# microbit-motion-tracking.net
KiCad netlist of a schematic drawn in Altium Designer
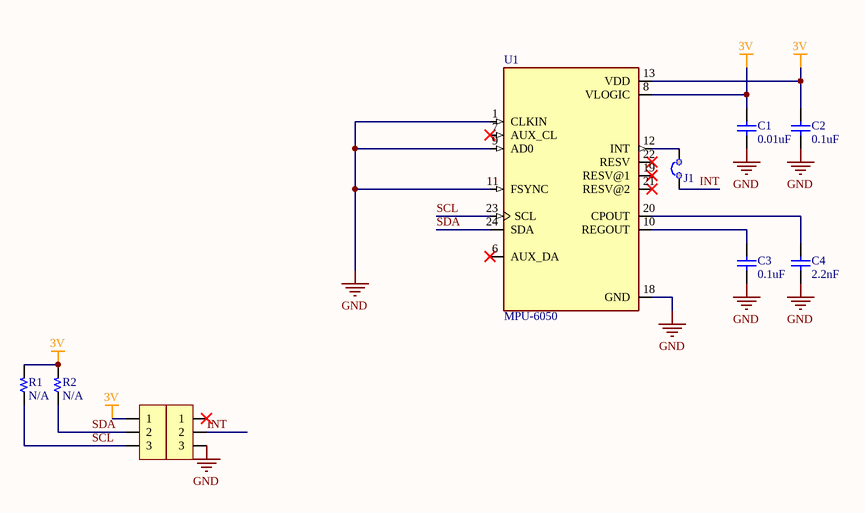
[diagram p0: microbit-motion-tracking.SchDoc]

(export (version "E")
  (design (tool "Eeschema 10.0.6"))
  (components
    (comp (ref "C1")
      (value "0.01uF")
      (footprint "C 0603")
      (description "Capacitor non-pol")
      (libsource (lib "common_altium_libs") (part "Capacitor NP"))
    )
    (comp (ref "C2")
      (value "0.1uF")
      (footprint "C 0603")
      (description "Capacitor non-pol")
      (libsource (lib "common_altium_libs") (part "Capacitor NP"))
    )
    (comp (ref "C3")
      (value "0.1uF")
      (footprint "C 0603")
      (description "Capacitor non-pol")
      (libsource (lib "common_altium_libs") (part "Capacitor NP"))
    )
    (comp (ref "C4")
      (value "2.2nF")
      (footprint "C 0603")
      (description "Capacitor non-pol")
      (libsource (lib "common_altium_libs") (part "Capacitor NP"))
    )
    (comp (ref "J1")
      (value "JUMP 2")
      (footprint "JUMP/2/SMD/D")
      (libsource (lib "common_altium_libs") (part "JUMP 2"))
    )
    (comp (ref "P1")
      (value "Header 3")
      (footprint "HDR/Header/3/c1")
      (description "Header, 3-Pin")
      (libsource (lib "common_altium_libs") (part "Header 3"))
    )
    (comp (ref "P2")
      (value "Header 3")
      (footprint "HDR/Header/3/c1")
      (description "Header, 3-Pin")
      (libsource (lib "") (part "Header 3_1"))
    )
    (comp (ref "R1")
      (value "N/A")
      (footprint "R 0603")
      (description "Resistor")
      (libsource (lib "common_altium_libs") (part "Resistor"))
    )
    (comp (ref "R2")
      (value "N/A")
      (footprint "R 0603")
      (description "Resistor")
      (libsource (lib "common_altium_libs") (part "Resistor"))
    )
    (comp (ref "U1")
      (value "MPU-6050")
      (footprint "QFN 50P 24 400X400X95")
      (description "Accelerometer, Gyroscope, 6 Axis Sensor IÂ²C Output")
      (fields (field (name "MF") "TDK InvenSense"))
      (libsource (lib "common_altium_libs") (part "MPU-6050"))
    )
  )
  (nets
    (net (code "1") (name "/INT") (class "Default")
      (node (ref "J1") (pin "1") (pinfunction "1_1") (pintype "passive"))
      (node (ref "P2") (pin "2") (pinfunction "2_2") (pintype "passive"))
    )
    (net (code "2") (name "/SCL") (class "Default")
      (node (ref "P1") (pin "3") (pinfunction "3_3") (pintype "passive"))
      (node (ref "R1") (pin "1") (pinfunction "1_1") (pintype "passive"))
      (node (ref "U1") (pin "23") (pinfunction "SCL_23") (pintype "input"))
    )
    (net (code "3") (name "/SDA") (class "Default")
      (node (ref "P1") (pin "2") (pinfunction "2_2") (pintype "passive"))
      (node (ref "R2") (pin "1") (pinfunction "1_1") (pintype "passive"))
      (node (ref "U1") (pin "24") (pinfunction "SDA_24") (pintype "bidirectional"))
    )
    (net (code "4") (name "3V") (class "Default")
      (node (ref "C1") (pin "1") (pinfunction "1_1") (pintype "passive"))
      (node (ref "C2") (pin "1") (pinfunction "1_1") (pintype "passive"))
      (node (ref "P1") (pin "1") (pinfunction "1_1") (pintype "passive"))
      (node (ref "R1") (pin "2") (pinfunction "2_2") (pintype "passive"))
      (node (ref "R2") (pin "2") (pinfunction "2_2") (pintype "passive"))
      (node (ref "U1") (pin "13") (pinfunction "VDD_13") (pintype "power_in"))
      (node (ref "U1") (pin "8") (pinfunction "VLOGIC_8") (pintype "power_in"))
    )
    (net (code "5") (name "GND") (class "Default")
      (node (ref "C1") (pin "2") (pinfunction "2_2") (pintype "passive"))
      (node (ref "C2") (pin "2") (pinfunction "2_2") (pintype "passive"))
      (node (ref "C3") (pin "2") (pinfunction "2_2") (pintype "passive"))
      (node (ref "C4") (pin "2") (pinfunction "2_2") (pintype "passive"))
      (node (ref "P2") (pin "3") (pinfunction "3_3") (pintype "passive"))
      (node (ref "U1") (pin "1") (pinfunction "CLKIN_1") (pintype "input"))
      (node (ref "U1") (pin "11") (pinfunction "FSYNC_11") (pintype "input"))
      (node (ref "U1") (pin "18") (pinfunction "GND_18") (pintype "power_in"))
      (node (ref "U1") (pin "9") (pinfunction "AD0_9") (pintype "input"))
    )
    (net (code "6") (name "Net-(U1-CPOUT)") (class "Default")
      (node (ref "C4") (pin "1") (pinfunction "1_1") (pintype "passive"))
      (node (ref "U1") (pin "20") (pinfunction "CPOUT_20") (pintype "passive"))
    )
    (net (code "7") (name "Net-(U1-INT)") (class "Default")
      (node (ref "J1") (pin "2") (pinfunction "2_2") (pintype "passive"))
      (node (ref "U1") (pin "12") (pinfunction "INT_12") (pintype "output"))
    )
    (net (code "8") (name "Net-(U1-REGOUT)") (class "Default")
      (node (ref "C3") (pin "1") (pinfunction "1_1") (pintype "passive"))
      (node (ref "U1") (pin "10") (pinfunction "REGOUT_10") (pintype "passive"))
    )
    (net (code "9") (name "unconnected-(P2-Pad1)") (class "Default")
      (node (ref "P2") (pin "1") (pinfunction "1_1") (pintype "passive+no_connect"))
    )
    (net (code "10") (name "unconnected-(U1-AUX_CL-Pad7)") (class "Default")
      (node (ref "U1") (pin "7") (pinfunction "AUX_CL_7") (pintype "input+no_connect"))
    )
    (net (code "11") (name "unconnected-(U1-AUX_DA-Pad6)") (class "Default")
      (node (ref "U1") (pin "6") (pinfunction "AUX_DA_6") (pintype "bidirectional+no_connect"))
    )
    (net (code "12") (name "unconnected-(U1-RESV-Pad22)") (class "Default")
      (node (ref "U1") (pin "22") (pinfunction "RESV_22") (pintype "passive+no_connect"))
    )
    (net (code "13") (name "unconnected-(U1-RESV@1-Pad19)") (class "Default")
      (node (ref "U1") (pin "19") (pinfunction "RESV@1_19") (pintype "passive+no_connect"))
    )
    (net (code "14") (name "unconnected-(U1-RESV@2-Pad21)") (class "Default")
      (node (ref "U1") (pin "21") (pinfunction "RESV@2_21") (pintype "passive+no_connect"))
    )
  )
)
